# Sheet1.net
KiCad netlist of a schematic drawn in Altium Designer
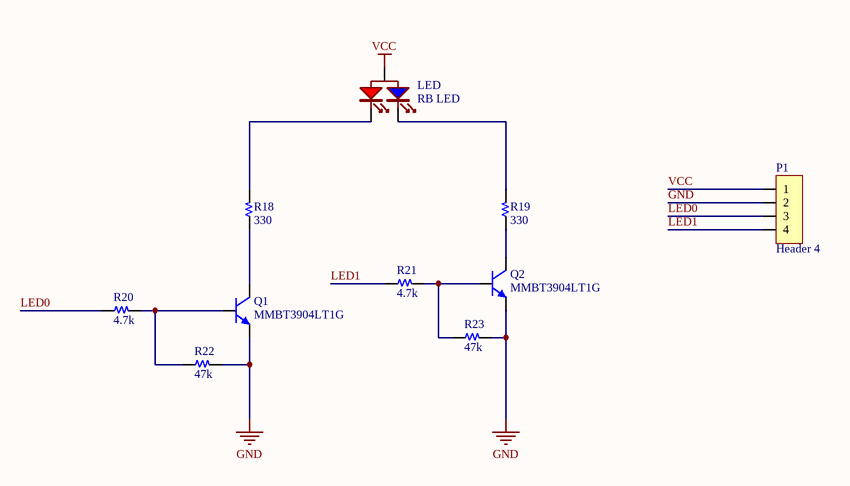
[diagram p0: Sheet1.SchDoc]

(export (version "E")
  (design (tool "Eeschema 10.0.6"))
  (components
    (comp (ref "LED")
      (value "RB LED")
      (footprint "LED-BICOLOR-3MM")
      (description "Bicolor RB 3mm LED")
      (libsource (lib "chipfc_altium_libs") (part "LED 2-color-A"))
    )
    (comp (ref "P1")
      (value "Header 4")
      (footprint "HDR/Header/4/BOX/RED")
      (description "Header, 4-Pin")
      (libsource (lib "chipfc_altium_libs") (part "Header 4"))
    )
    (comp (ref "Q1")
      (value "MMBT3904LT1G")
      (footprint "SOT-23")
      (description "NPN Bipolar Transistor")
      (libsource (lib "chipfc_altium_libs") (part "Transistor NPN"))
    )
    (comp (ref "Q2")
      (value "MMBT3904LT1G")
      (footprint "SOT-23")
      (description "NPN Bipolar Transistor")
      (libsource (lib "chipfc_altium_libs") (part "Transistor NPN"))
    )
    (comp (ref "R18")
      (value "330")
      (footprint "R 0603")
      (description "Resistor")
      (libsource (lib "chipfc_altium_libs") (part "Resistor"))
    )
    (comp (ref "R19")
      (value "330")
      (footprint "R 0603")
      (description "Resistor")
      (libsource (lib "chipfc_altium_libs") (part "Resistor"))
    )
    (comp (ref "R20")
      (value "4.7k")
      (footprint "R 0603")
      (description "Resistor")
      (libsource (lib "chipfc_altium_libs") (part "Resistor"))
    )
    (comp (ref "R21")
      (value "4.7k")
      (footprint "R 0603")
      (description "Resistor")
      (libsource (lib "chipfc_altium_libs") (part "Resistor"))
    )
    (comp (ref "R22")
      (value "47k")
      (footprint "R 0603")
      (description "Resistor")
      (libsource (lib "chipfc_altium_libs") (part "Resistor"))
    )
    (comp (ref "R23")
      (value "47k")
      (footprint "R 0603")
      (description "Resistor")
      (libsource (lib "chipfc_altium_libs") (part "Resistor"))
    )
  )
  (nets
    (net (code "1") (name "/LED0") (class "Default")
      (node (ref "P1") (pin "3") (pinfunction "3_3") (pintype "passive"))
      (node (ref "R20") (pin "1") (pinfunction "1_1") (pintype "passive"))
    )
    (net (code "2") (name "/LED1") (class "Default")
      (node (ref "P1") (pin "4") (pinfunction "4_4") (pintype "passive"))
      (node (ref "R21") (pin "1") (pinfunction "1_1") (pintype "passive"))
    )
    (net (code "3") (name "GND") (class "Default")
      (node (ref "P1") (pin "2") (pinfunction "2_2") (pintype "passive"))
      (node (ref "Q1") (pin "2") (pinfunction "E_2") (pintype "passive"))
      (node (ref "Q2") (pin "2") (pinfunction "E_2") (pintype "passive"))
      (node (ref "R22") (pin "2") (pinfunction "2_2") (pintype "passive"))
      (node (ref "R23") (pin "2") (pinfunction "2_2") (pintype "passive"))
    )
    (net (code "4") (name "Net-(LED-K1)") (class "Default")
      (node (ref "LED") (pin "1") (pinfunction "K1_1") (pintype "passive"))
      (node (ref "R18") (pin "2") (pinfunction "2_2") (pintype "passive"))
    )
    (net (code "5") (name "Net-(LED-K2)") (class "Default")
      (node (ref "LED") (pin "3") (pinfunction "K2_3") (pintype "passive"))
      (node (ref "R19") (pin "2") (pinfunction "2_2") (pintype "passive"))
    )
    (net (code "6") (name "Net-(Q1-B)") (class "Default")
      (node (ref "Q1") (pin "1") (pinfunction "B_1") (pintype "passive"))
      (node (ref "R20") (pin "2") (pinfunction "2_2") (pintype "passive"))
      (node (ref "R22") (pin "1") (pinfunction "1_1") (pintype "passive"))
    )
    (net (code "7") (name "Net-(Q1-C)") (class "Default")
      (node (ref "Q1") (pin "3") (pinfunction "C_3") (pintype "passive"))
      (node (ref "R18") (pin "1") (pinfunction "1_1") (pintype "passive"))
    )
    (net (code "8") (name "Net-(Q2-B)") (class "Default")
      (node (ref "Q2") (pin "1") (pinfunction "B_1") (pintype "passive"))
      (node (ref "R21") (pin "2") (pinfunction "2_2") (pintype "passive"))
      (node (ref "R23") (pin "1") (pinfunction "1_1") (pintype "passive"))
    )
    (net (code "9") (name "Net-(Q2-C)") (class "Default")
      (node (ref "Q2") (pin "3") (pinfunction "C_3") (pintype "passive"))
      (node (ref "R19") (pin "1") (pinfunction "1_1") (pintype "passive"))
    )
    (net (code "10") (name "VCC") (class "Default")
      (node (ref "LED") (pin "2") (pinfunction "A_2") (pintype "passive"))
      (node (ref "P1") (pin "1") (pinfunction "1_1") (pintype "passive"))
    )
  )
)
